# Gyrocam_Servo_Driver_STM32G070KBT6.net
KiCad netlist of a schematic drawn in EAGLE
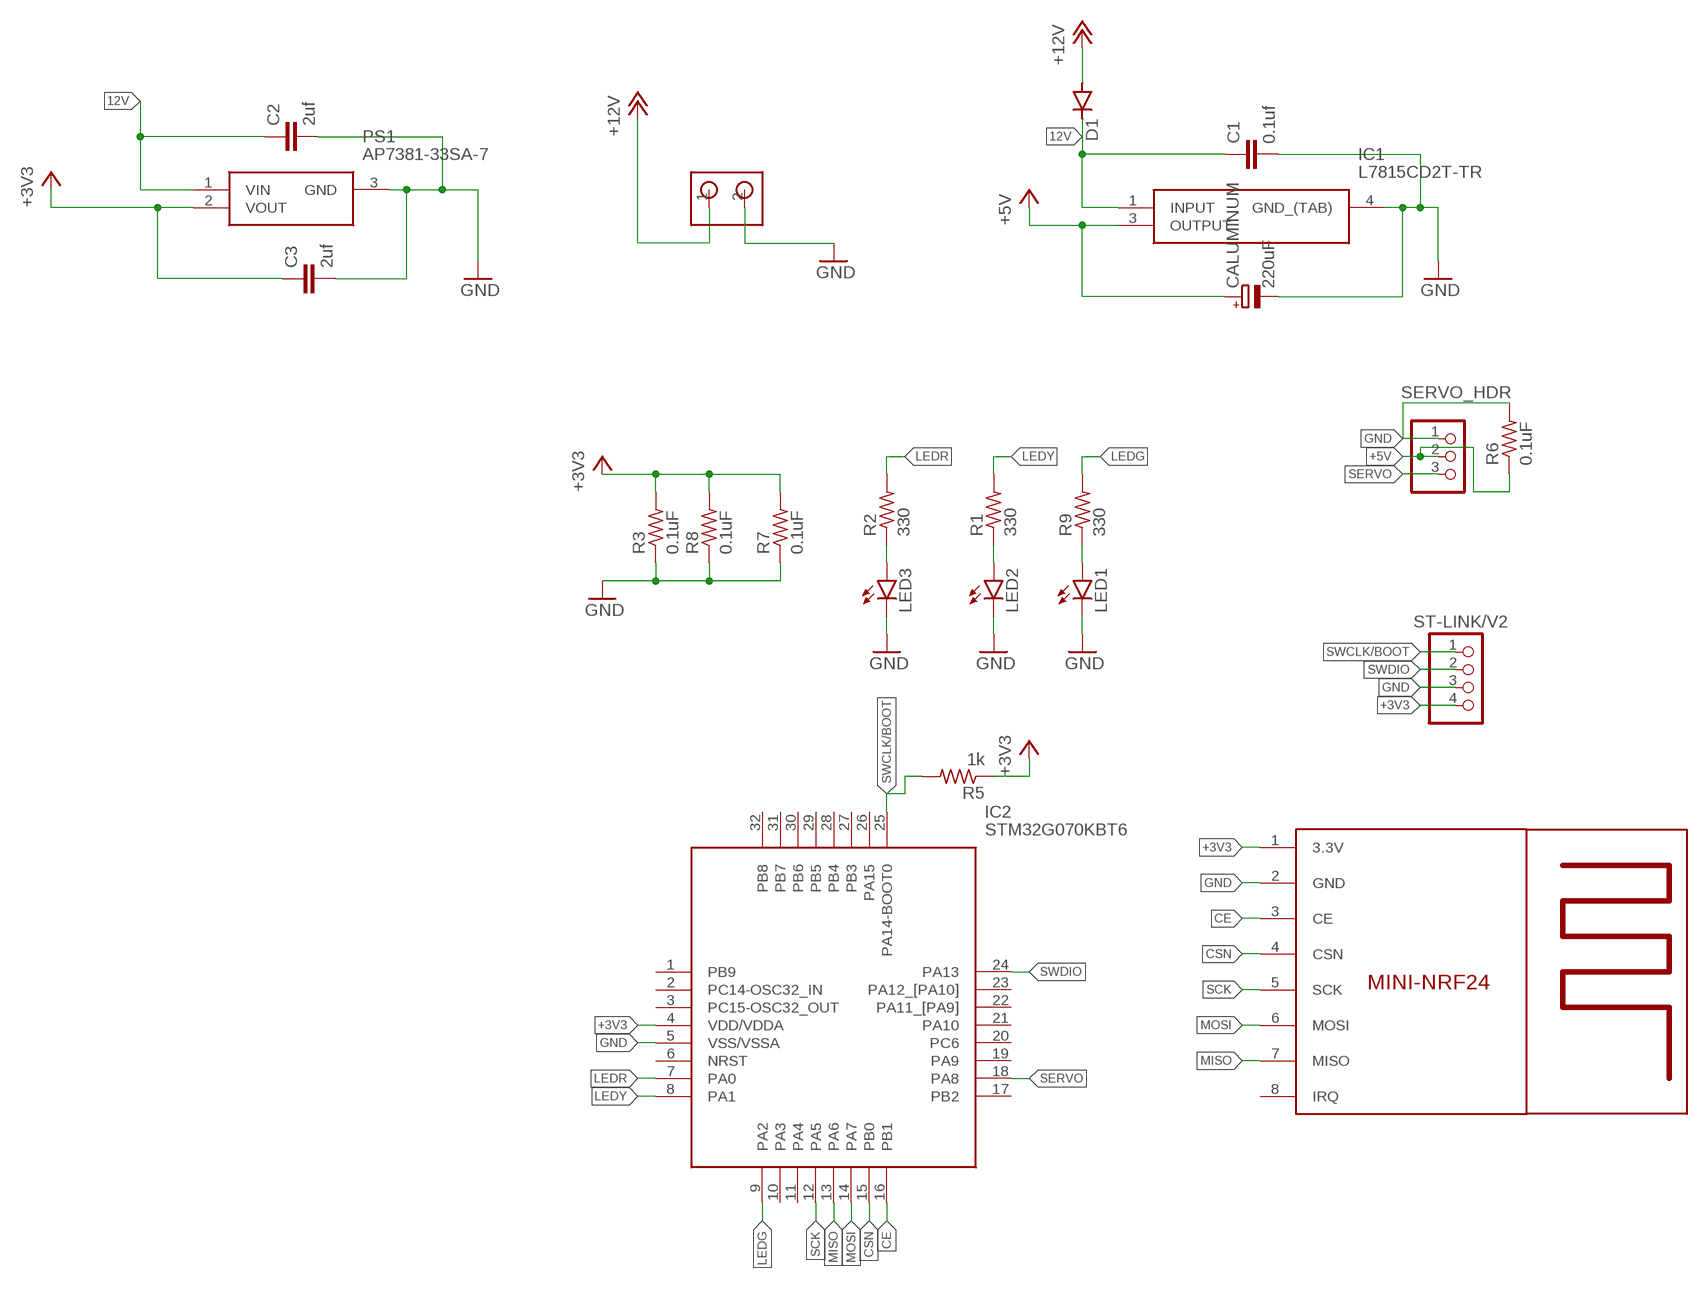
[diagram p0: schematic, sheet 1]

(export (version "E")
  (design (tool "Eeschema 10.0.6"))
  (components
    (comp (ref "C1")
      (value "0.1uf")
      (footprint "eagle-import:C0805K")
      (libsource (lib "eagle-import") (part "C-EUC0805K"))
    )
    (comp (ref "C2")
      (value "2uf")
      (footprint "eagle-import:C0805K")
      (libsource (lib "eagle-import") (part "C-EUC0805K"))
    )
    (comp (ref "C3")
      (value "2uf")
      (footprint "eagle-import:C0805K")
      (libsource (lib "eagle-import") (part "C-EUC0805K"))
    )
    (comp (ref "CALUMINUM")
      (value "220uF")
      (footprint "eagle-import:153CLV-0810")
      (libsource (lib "eagle-import") (part "CPOL-EU153CLV-0810"))
    )
    (comp (ref "D1")
      (value "DIODE-DO-214AC")
      (footprint "eagle-import:DO-214AC")
      (libsource (lib "eagle-import") (part "DIODE-DO-214AC"))
    )
    (comp (ref "IC1")
      (value "L7815CD2T-TR")
      (footprint "eagle-import:TO254P1542X460-3N")
      (fields (field (name "MOUSER_PART_NUMBER") "511-L7815CD2T-TR"))
      (libsource (lib "eagle-import") (part "L7815CD2T-TR"))
    )
    (comp (ref "IC2")
      (value "STM32G070KBT6")
      (footprint "eagle-import:QFP80P900X900X160-32N")
      (fields (field (name "MOUSER_PART_NUMBER") "511-STM32G070KBT6"))
      (libsource (lib "eagle-import") (part "STM32G070KBT6"))
    )
    (comp (ref "LED1")
      (value "LEDSML0805")
      (footprint "eagle-import:SML0805")
      (libsource (lib "eagle-import") (part "LEDSML0805"))
    )
    (comp (ref "LED2")
      (value "LEDSML0805")
      (footprint "eagle-import:SML0805")
      (libsource (lib "eagle-import") (part "LEDSML0805"))
    )
    (comp (ref "LED3")
      (value "LEDSML0805")
      (footprint "eagle-import:SML0805")
      (libsource (lib "eagle-import") (part "LEDSML0805"))
    )
    (comp (ref "PS1")
      (value "AP7381-33SA-7")
      (footprint "eagle-import:SOT96P240X120-3N")
      (fields (field (name "MOUSER_PART_NUMBER") "621-AP7381-33SA-7"))
      (libsource (lib "eagle-import") (part "AP7381-33SA-7"))
    )
    (comp (ref "R1")
      (value "330")
      (footprint "eagle-import:R0805")
      (libsource (lib "eagle-import") (part "R-US_R0805"))
    )
    (comp (ref "R2")
      (value "330")
      (footprint "eagle-import:R0805")
      (libsource (lib "eagle-import") (part "R-US_R0805"))
    )
    (comp (ref "R3")
      (value "0.1uF")
      (footprint "eagle-import:R0805")
      (libsource (lib "eagle-import") (part "R-US_R0805"))
    )
    (comp (ref "R5")
      (value "1k")
      (footprint "eagle-import:R0805")
      (libsource (lib "eagle-import") (part "R-US_R0805"))
    )
    (comp (ref "R6")
      (value "0.1uF")
      (footprint "eagle-import:R0805")
      (libsource (lib "eagle-import") (part "R-US_R0805"))
    )
    (comp (ref "R7")
      (value "0.1uF")
      (footprint "eagle-import:R0805")
      (libsource (lib "eagle-import") (part "R-US_R0805"))
    )
    (comp (ref "R8")
      (value "0.1uF")
      (footprint "eagle-import:R0805")
      (libsource (lib "eagle-import") (part "R-US_R0805"))
    )
    (comp (ref "R9")
      (value "330")
      (footprint "eagle-import:R0805")
      (libsource (lib "eagle-import") (part "R-US_R0805"))
    )
    (comp (ref "SERVO_HDR")
      (value "PINHD-1X3")
      (footprint "eagle-import:1X03")
      (libsource (lib "eagle-import") (part "PINHD-1X3"))
    )
    (comp (ref "ST-LINK/V2")
      (value "PINHD-1X4")
      (footprint "eagle-import:1X04")
      (libsource (lib "eagle-import") (part "PINHD-1X4"))
    )
    (comp (ref "U$2")
      (value "MINI-NRF24L01PSMD")
      (footprint "eagle-import:NRF24L01_SMD")
      (libsource (lib "eagle-import") (part "MINI-NRF24L01PSMD"))
    )
    (comp (ref "U$5")
      (value "PINHEAD2_18AAWG")
      (footprint "eagle-import:PINHEAD2_18AWG")
      (libsource (lib "eagle-import") (part "PINHEAD2_18AAWG"))
    )
  )
  (nets
    (net (code "1") (name "+3V3") (class "Default")
      (node (ref "C3") (pin "1") (pinfunction "1_1") (pintype "passive"))
      (node (ref "IC2") (pin "4") (pinfunction "VDD/VDDA_4") (pintype "power_in"))
      (node (ref "PS1") (pin "2") (pinfunction "VOUT_2") (pintype "bidirectional"))
      (node (ref "R3") (pin "2") (pinfunction "2_2") (pintype "passive"))
      (node (ref "R5") (pin "1") (pinfunction "1_1") (pintype "passive"))
      (node (ref "R7") (pin "2") (pinfunction "2_2") (pintype "passive"))
      (node (ref "R8") (pin "2") (pinfunction "2_2") (pintype "passive"))
      (node (ref "ST-LINK/V2") (pin "4") (pinfunction "4_4") (pintype "passive"))
      (node (ref "U$2") (pin "1") (pinfunction "3.3V_1") (pintype "bidirectional"))
    )
    (net (code "2") (name "+5V") (class "Default")
      (node (ref "CALUMINUM") (pin "+") (pinfunction "+_+") (pintype "passive"))
      (node (ref "IC1") (pin "3") (pinfunction "OUTPUT_3") (pintype "power_in"))
      (node (ref "R6") (pin "1") (pinfunction "1_1") (pintype "passive"))
      (node (ref "SERVO_HDR") (pin "2") (pinfunction "2_2") (pintype "passive"))
    )
    (net (code "3") (name "+12V") (class "Default")
      (node (ref "D1") (pin "A") (pinfunction "A_A") (pintype "passive"))
      (node (ref "U$5") (pin "1") (pinfunction "1_1") (pintype "bidirectional"))
    )
    (net (code "4") (name "12V") (class "Default")
      (node (ref "C1") (pin "1") (pinfunction "1_1") (pintype "passive"))
      (node (ref "C2") (pin "1") (pinfunction "1_1") (pintype "passive"))
      (node (ref "D1") (pin "C") (pinfunction "C_C") (pintype "passive"))
      (node (ref "IC1") (pin "1") (pinfunction "INPUT_1") (pintype "output"))
      (node (ref "PS1") (pin "1") (pinfunction "VIN_1") (pintype "bidirectional"))
    )
    (net (code "5") (name "CE") (class "Default")
      (node (ref "IC2") (pin "16") (pinfunction "PB1_16") (pintype "bidirectional"))
      (node (ref "U$2") (pin "3") (pinfunction "CE_3") (pintype "bidirectional"))
    )
    (net (code "6") (name "CSN") (class "Default")
      (node (ref "IC2") (pin "15") (pinfunction "PB0_15") (pintype "bidirectional"))
      (node (ref "U$2") (pin "4") (pinfunction "CSN_4") (pintype "bidirectional"))
    )
    (net (code "7") (name "GND") (class "Default")
      (node (ref "C1") (pin "2") (pinfunction "2_2") (pintype "passive"))
      (node (ref "C2") (pin "2") (pinfunction "2_2") (pintype "passive"))
      (node (ref "C3") (pin "2") (pinfunction "2_2") (pintype "passive"))
      (node (ref "CALUMINUM") (pin "-") (pinfunction "-_-") (pintype "passive"))
      (node (ref "IC1") (pin "4") (pinfunction "GND_(TAB)_4") (pintype "input"))
      (node (ref "IC2") (pin "5") (pinfunction "VSS/VSSA_5") (pintype "power_in"))
      (node (ref "LED1") (pin "C") (pinfunction "C_C") (pintype "passive"))
      (node (ref "LED2") (pin "C") (pinfunction "C_C") (pintype "passive"))
      (node (ref "LED3") (pin "C") (pinfunction "C_C") (pintype "passive"))
      (node (ref "PS1") (pin "3") (pinfunction "GND_3") (pintype "bidirectional"))
      (node (ref "R3") (pin "1") (pinfunction "1_1") (pintype "passive"))
      (node (ref "R6") (pin "2") (pinfunction "2_2") (pintype "passive"))
      (node (ref "R7") (pin "1") (pinfunction "1_1") (pintype "passive"))
      (node (ref "R8") (pin "1") (pinfunction "1_1") (pintype "passive"))
      (node (ref "SERVO_HDR") (pin "1") (pinfunction "1_1") (pintype "passive"))
      (node (ref "ST-LINK/V2") (pin "3") (pinfunction "3_3") (pintype "passive"))
      (node (ref "U$2") (pin "2") (pinfunction "GND_2") (pintype "bidirectional"))
      (node (ref "U$5") (pin "2") (pinfunction "2_2") (pintype "bidirectional"))
    )
    (net (code "8") (name "LEDG") (class "Default")
      (node (ref "IC2") (pin "9") (pinfunction "PA2_9") (pintype "bidirectional"))
      (node (ref "R9") (pin "2") (pinfunction "2_2") (pintype "passive"))
    )
    (net (code "9") (name "LEDR") (class "Default")
      (node (ref "IC2") (pin "7") (pinfunction "PA0_7") (pintype "bidirectional"))
      (node (ref "R2") (pin "2") (pinfunction "2_2") (pintype "passive"))
    )
    (net (code "10") (name "LEDY") (class "Default")
      (node (ref "IC2") (pin "8") (pinfunction "PA1_8") (pintype "bidirectional"))
      (node (ref "R1") (pin "2") (pinfunction "2_2") (pintype "passive"))
    )
    (net (code "11") (name "MISO") (class "Default")
      (node (ref "IC2") (pin "13") (pinfunction "PA6_13") (pintype "bidirectional"))
      (node (ref "U$2") (pin "7") (pinfunction "MISO_7") (pintype "bidirectional"))
    )
    (net (code "12") (name "MOSI") (class "Default")
      (node (ref "IC2") (pin "14") (pinfunction "PA7_14") (pintype "bidirectional"))
      (node (ref "U$2") (pin "6") (pinfunction "MOSI_6") (pintype "bidirectional"))
    )
    (net (code "13") (name "Net-(LED1-PadA)") (class "Default")
      (node (ref "LED1") (pin "A") (pinfunction "A_A") (pintype "passive"))
      (node (ref "R9") (pin "1") (pinfunction "1_1") (pintype "passive"))
    )
    (net (code "14") (name "Net-(LED2-PadA)") (class "Default")
      (node (ref "LED2") (pin "A") (pinfunction "A_A") (pintype "passive"))
      (node (ref "R1") (pin "1") (pinfunction "1_1") (pintype "passive"))
    )
    (net (code "15") (name "Net-(LED3-PadA)") (class "Default")
      (node (ref "LED3") (pin "A") (pinfunction "A_A") (pintype "passive"))
      (node (ref "R2") (pin "1") (pinfunction "1_1") (pintype "passive"))
    )
    (net (code "16") (name "SCK") (class "Default")
      (node (ref "IC2") (pin "12") (pinfunction "PA5_12") (pintype "bidirectional"))
      (node (ref "U$2") (pin "5") (pinfunction "SCK_5") (pintype "bidirectional"))
    )
    (net (code "17") (name "SERVO") (class "Default")
      (node (ref "IC2") (pin "18") (pinfunction "PA8_18") (pintype "bidirectional"))
      (node (ref "SERVO_HDR") (pin "3") (pinfunction "3_3") (pintype "passive"))
    )
    (net (code "18") (name "SWCLK{slash}BOOT") (class "Default")
      (node (ref "IC2") (pin "25") (pinfunction "PA14-BOOT0_25") (pintype "bidirectional"))
      (node (ref "R5") (pin "2") (pinfunction "2_2") (pintype "passive"))
      (node (ref "ST-LINK/V2") (pin "1") (pinfunction "1_1") (pintype "passive"))
    )
    (net (code "19") (name "SWDIO") (class "Default")
      (node (ref "IC2") (pin "24") (pinfunction "PA13_24") (pintype "bidirectional"))
      (node (ref "ST-LINK/V2") (pin "2") (pinfunction "2_2") (pintype "passive"))
    )
    (net (code "20") (name "unconnected-(IC2-NRST-Pad6)") (class "Default")
      (node (ref "IC2") (pin "6") (pinfunction "NRST_6") (pintype "bidirectional"))
    )
    (net (code "21") (name "unconnected-(IC2-PA3-Pad10)") (class "Default")
      (node (ref "IC2") (pin "10") (pinfunction "PA3_10") (pintype "bidirectional"))
    )
    (net (code "22") (name "unconnected-(IC2-PA4-Pad11)") (class "Default")
      (node (ref "IC2") (pin "11") (pinfunction "PA4_11") (pintype "bidirectional"))
    )
    (net (code "23") (name "unconnected-(IC2-PA9-Pad19)") (class "Default")
      (node (ref "IC2") (pin "19") (pinfunction "PA9_19") (pintype "bidirectional"))
    )
    (net (code "24") (name "unconnected-(IC2-PA10-Pad21)") (class "Default")
      (node (ref "IC2") (pin "21") (pinfunction "PA10_21") (pintype "bidirectional"))
    )
    (net (code "25") (name "unconnected-(IC2-PA11_[PA9]-Pad22)") (class "Default")
      (node (ref "IC2") (pin "22") (pinfunction "PA11_[PA9]_22") (pintype "bidirectional"))
    )
    (net (code "26") (name "unconnected-(IC2-PA12_[PA10]-Pad23)") (class "Default")
      (node (ref "IC2") (pin "23") (pinfunction "PA12_[PA10]_23") (pintype "bidirectional"))
    )
    (net (code "27") (name "unconnected-(IC2-PA15-Pad26)") (class "Default")
      (node (ref "IC2") (pin "26") (pinfunction "PA15_26") (pintype "bidirectional"))
    )
    (net (code "28") (name "unconnected-(IC2-PB2-Pad17)") (class "Default")
      (node (ref "IC2") (pin "17") (pinfunction "PB2_17") (pintype "bidirectional"))
    )
    (net (code "29") (name "unconnected-(IC2-PB3-Pad27)") (class "Default")
      (node (ref "IC2") (pin "27") (pinfunction "PB3_27") (pintype "bidirectional"))
    )
    (net (code "30") (name "unconnected-(IC2-PB4-Pad28)") (class "Default")
      (node (ref "IC2") (pin "28") (pinfunction "PB4_28") (pintype "bidirectional"))
    )
    (net (code "31") (name "unconnected-(IC2-PB5-Pad29)") (class "Default")
      (node (ref "IC2") (pin "29") (pinfunction "PB5_29") (pintype "bidirectional"))
    )
    (net (code "32") (name "unconnected-(IC2-PB6-Pad30)") (class "Default")
      (node (ref "IC2") (pin "30") (pinfunction "PB6_30") (pintype "bidirectional"))
    )
    (net (code "33") (name "unconnected-(IC2-PB7-Pad31)") (class "Default")
      (node (ref "IC2") (pin "31") (pinfunction "PB7_31") (pintype "bidirectional"))
    )
    (net (code "34") (name "unconnected-(IC2-PB8-Pad32)") (class "Default")
      (node (ref "IC2") (pin "32") (pinfunction "PB8_32") (pintype "bidirectional"))
    )
    (net (code "35") (name "unconnected-(IC2-PB9-Pad1)") (class "Default")
      (node (ref "IC2") (pin "1") (pinfunction "PB9_1") (pintype "bidirectional"))
    )
    (net (code "36") (name "unconnected-(IC2-PC6-Pad20)") (class "Default")
      (node (ref "IC2") (pin "20") (pinfunction "PC6_20") (pintype "bidirectional"))
    )
    (net (code "37") (name "unconnected-(IC2-PC14-OSC32_IN-Pad2)") (class "Default")
      (node (ref "IC2") (pin "2") (pinfunction "PC14-OSC32_IN_2") (pintype "bidirectional"))
    )
    (net (code "38") (name "unconnected-(IC2-PC15-OSC32_OUT-Pad3)") (class "Default")
      (node (ref "IC2") (pin "3") (pinfunction "PC15-OSC32_OUT_3") (pintype "bidirectional"))
    )
    (net (code "39") (name "unconnected-(U$2-IRQ-Pad8)") (class "Default")
      (node (ref "U$2") (pin "8") (pinfunction "IRQ_8") (pintype "bidirectional"))
    )
  )
)
